# WakeOnWifi.net
KiCad netlist of a schematic drawn in EAGLE
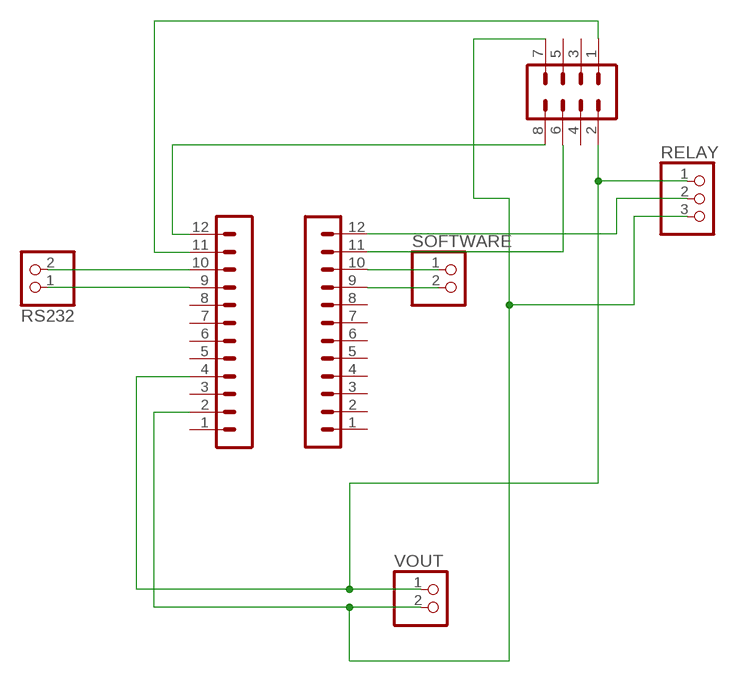
[diagram p0: schematic, sheet 1]

(export (version "E")
  (design (tool "Eeschema 10.0.6"))
  (components
    (comp (ref "ARDUINOLEFT")
      (value "MA12-1")
      (footprint "eagle-import:MA12-1")
      (libsource (lib "eagle-import") (part "MA12-1"))
    )
    (comp (ref "ARDUINORIGHT")
      (value "MA12-1")
      (footprint "eagle-import:MA12-1")
      (libsource (lib "eagle-import") (part "MA12-1"))
    )
    (comp (ref "RELAY")
      (value "PINHD-1X3")
      (footprint "eagle-import:1X03")
      (libsource (lib "eagle-import") (part "PINHD-1X3"))
    )
    (comp (ref "RS232")
      (value "PINHD-1X2")
      (footprint "eagle-import:1X02")
      (libsource (lib "eagle-import") (part "PINHD-1X2"))
    )
    (comp (ref "SOFTWARE")
      (value "PINHD-1X2")
      (footprint "eagle-import:1X02")
      (libsource (lib "eagle-import") (part "PINHD-1X2"))
    )
    (comp (ref "VOUT")
      (value "PINHD-1X2")
      (footprint "eagle-import:1X02")
      (libsource (lib "eagle-import") (part "PINHD-1X2"))
    )
    (comp (ref "WIFI")
      (value "MA04-2")
      (footprint "eagle-import:MA04-2")
      (libsource (lib "eagle-import") (part "MA04-2"))
    )
  )
  (nets
    (net (code "1") (name "Net-(ARDUINOLEFT-Pad2)") (class "Default")
      (node (ref "ARDUINOLEFT") (pin "2") (pinfunction "2_2") (pintype "passive"))
      (node (ref "RELAY") (pin "3") (pinfunction "3_3") (pintype "passive"))
      (node (ref "VOUT") (pin "2") (pinfunction "2_2") (pintype "passive"))
      (node (ref "WIFI") (pin "7") (pinfunction "7_7") (pintype "passive"))
    )
    (net (code "2") (name "Net-(ARDUINOLEFT-Pad4)") (class "Default")
      (node (ref "ARDUINOLEFT") (pin "4") (pinfunction "4_4") (pintype "passive"))
      (node (ref "RELAY") (pin "1") (pinfunction "1_1") (pintype "passive"))
      (node (ref "VOUT") (pin "1") (pinfunction "1_1") (pintype "passive"))
      (node (ref "WIFI") (pin "2") (pinfunction "2_2") (pintype "passive"))
    )
    (net (code "3") (name "Net-(ARDUINOLEFT-Pad9)") (class "Default")
      (node (ref "ARDUINOLEFT") (pin "9") (pinfunction "9_9") (pintype "passive"))
      (node (ref "RS232") (pin "1") (pinfunction "1_1") (pintype "passive"))
    )
    (net (code "4") (name "Net-(ARDUINOLEFT-Pad10)") (class "Default")
      (node (ref "ARDUINOLEFT") (pin "10") (pinfunction "10_10") (pintype "passive"))
      (node (ref "RS232") (pin "2") (pinfunction "2_2") (pintype "passive"))
    )
    (net (code "5") (name "Net-(ARDUINOLEFT-Pad11)") (class "Default")
      (node (ref "ARDUINOLEFT") (pin "11") (pinfunction "11_11") (pintype "passive"))
      (node (ref "WIFI") (pin "1") (pinfunction "1_1") (pintype "passive"))
    )
    (net (code "6") (name "Net-(ARDUINOLEFT-Pad12)") (class "Default")
      (node (ref "ARDUINOLEFT") (pin "12") (pinfunction "12_12") (pintype "passive"))
      (node (ref "WIFI") (pin "8") (pinfunction "8_8") (pintype "passive"))
    )
    (net (code "7") (name "Net-(ARDUINORIGHT-Pad9)") (class "Default")
      (node (ref "ARDUINORIGHT") (pin "9") (pinfunction "9_9") (pintype "passive"))
      (node (ref "SOFTWARE") (pin "2") (pinfunction "2_2") (pintype "passive"))
    )
    (net (code "8") (name "Net-(ARDUINORIGHT-Pad10)") (class "Default")
      (node (ref "ARDUINORIGHT") (pin "10") (pinfunction "10_10") (pintype "passive"))
      (node (ref "SOFTWARE") (pin "1") (pinfunction "1_1") (pintype "passive"))
    )
    (net (code "9") (name "Net-(ARDUINORIGHT-Pad11)") (class "Default")
      (node (ref "ARDUINORIGHT") (pin "11") (pinfunction "11_11") (pintype "passive"))
      (node (ref "WIFI") (pin "6") (pinfunction "6_6") (pintype "passive"))
    )
    (net (code "10") (name "Net-(ARDUINORIGHT-Pad12)") (class "Default")
      (node (ref "ARDUINORIGHT") (pin "12") (pinfunction "12_12") (pintype "passive"))
      (node (ref "RELAY") (pin "2") (pinfunction "2_2") (pintype "passive"))
    )
    (net (code "11") (name "unconnected-(ARDUINOLEFT-Pad1)") (class "Default")
      (node (ref "ARDUINOLEFT") (pin "1") (pinfunction "1_1") (pintype "passive"))
    )
    (net (code "12") (name "unconnected-(ARDUINOLEFT-Pad3)") (class "Default")
      (node (ref "ARDUINOLEFT") (pin "3") (pinfunction "3_3") (pintype "passive"))
    )
    (net (code "13") (name "unconnected-(ARDUINOLEFT-Pad5)") (class "Default")
      (node (ref "ARDUINOLEFT") (pin "5") (pinfunction "5_5") (pintype "passive"))
    )
    (net (code "14") (name "unconnected-(ARDUINOLEFT-Pad6)") (class "Default")
      (node (ref "ARDUINOLEFT") (pin "6") (pinfunction "6_6") (pintype "passive"))
    )
    (net (code "15") (name "unconnected-(ARDUINOLEFT-Pad7)") (class "Default")
      (node (ref "ARDUINOLEFT") (pin "7") (pinfunction "7_7") (pintype "passive"))
    )
    (net (code "16") (name "unconnected-(ARDUINOLEFT-Pad8)") (class "Default")
      (node (ref "ARDUINOLEFT") (pin "8") (pinfunction "8_8") (pintype "passive"))
    )
    (net (code "17") (name "unconnected-(ARDUINORIGHT-Pad1)") (class "Default")
      (node (ref "ARDUINORIGHT") (pin "1") (pinfunction "1_1") (pintype "passive"))
    )
    (net (code "18") (name "unconnected-(ARDUINORIGHT-Pad2)") (class "Default")
      (node (ref "ARDUINORIGHT") (pin "2") (pinfunction "2_2") (pintype "passive"))
    )
    (net (code "19") (name "unconnected-(ARDUINORIGHT-Pad3)") (class "Default")
      (node (ref "ARDUINORIGHT") (pin "3") (pinfunction "3_3") (pintype "passive"))
    )
    (net (code "20") (name "unconnected-(ARDUINORIGHT-Pad4)") (class "Default")
      (node (ref "ARDUINORIGHT") (pin "4") (pinfunction "4_4") (pintype "passive"))
    )
    (net (code "21") (name "unconnected-(ARDUINORIGHT-Pad5)") (class "Default")
      (node (ref "ARDUINORIGHT") (pin "5") (pinfunction "5_5") (pintype "passive"))
    )
    (net (code "22") (name "unconnected-(ARDUINORIGHT-Pad6)") (class "Default")
      (node (ref "ARDUINORIGHT") (pin "6") (pinfunction "6_6") (pintype "passive"))
    )
    (net (code "23") (name "unconnected-(ARDUINORIGHT-Pad7)") (class "Default")
      (node (ref "ARDUINORIGHT") (pin "7") (pinfunction "7_7") (pintype "passive"))
    )
    (net (code "24") (name "unconnected-(ARDUINORIGHT-Pad8)") (class "Default")
      (node (ref "ARDUINORIGHT") (pin "8") (pinfunction "8_8") (pintype "passive"))
    )
    (net (code "25") (name "unconnected-(WIFI-Pad3)") (class "Default")
      (node (ref "WIFI") (pin "3") (pinfunction "3_3") (pintype "passive"))
    )
    (net (code "26") (name "unconnected-(WIFI-Pad4)") (class "Default")
      (node (ref "WIFI") (pin "4") (pinfunction "4_4") (pintype "passive"))
    )
    (net (code "27") (name "unconnected-(WIFI-Pad5)") (class "Default")
      (node (ref "WIFI") (pin "5") (pinfunction "5_5") (pintype "passive"))
    )
  )
)
